# mpu9250.net
KiCad netlist of a schematic drawn in Altium Designer
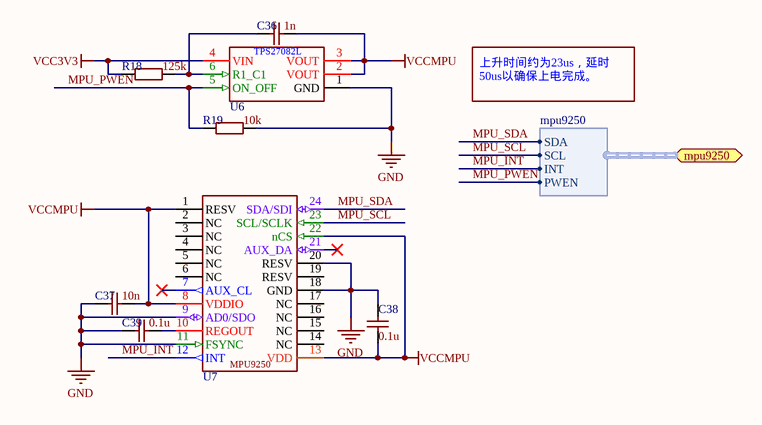
[diagram p0: mpu9250.SchDoc]

(export (version "E")
  (design (tool "Eeschema 10.0.6"))
  (components
    (comp (ref "C36")
      (value "1n")
      (footprint "C0402_h")
      (description "Capacitor")
      (fields (field (name "PUBLISHER") "Altium Limited"))
      (libsource (lib "电子元件封装库") (part "贴片电容-无极性"))
    )
    (comp (ref "C37")
      (value "10n")
      (footprint "C0402_h")
      (description "Capacitor")
      (fields (field (name "PUBLISHER") "Altium Limited"))
      (libsource (lib "电子元件封装库") (part "贴片电容-无极性"))
    )
    (comp (ref "C38")
      (value "0.1u")
      (footprint "C0402_h")
      (description "Capacitor")
      (fields (field (name "PUBLISHER") "Altium Limited"))
      (libsource (lib "电子元件封装库") (part "贴片电容-无极性"))
    )
    (comp (ref "C39")
      (value "0.1u")
      (footprint "C0402_h")
      (description "Capacitor")
      (fields (field (name "PUBLISHER") "Altium Limited"))
      (libsource (lib "电子元件封装库") (part "贴片电容-无极性"))
    )
    (comp (ref "R18")
      (value "125k")
      (footprint "R0402")
      (description "Register")
      (libsource (lib "电子元件封装库") (part "贴片电阻"))
    )
    (comp (ref "R19")
      (value "10k")
      (footprint "R0402")
      (description "Register")
      (libsource (lib "电子元件封装库") (part "贴片电阻"))
    )
    (comp (ref "U6")
      (value "TPS27082L")
      (footprint "SOT23-6")
      (description "load switch")
      (fields (field (name "PARTNUMBER") "TPS27082LDDC") (field (name "MANUFACTURER") "Texas Instruments"))
      (libsource (lib "电子元件封装库") (part "TPS27082LDDCR"))
    )
    (comp (ref "U7")
      (value "MPU9250")
      (footprint "QFN24 3.0X3.0")
      (description "9-axis MotionTracking Sensor")
      (libsource (lib "电子元件封装库") (part "MPU9250"))
    )
  )
  (nets
    (net (code "2") (name "/MPU_INT") (class "Default")
      (node (ref "U7") (pin "12") (pinfunction "INT_12") (pintype "output"))
    )
    (net (code "3") (name "/MPU_PWEN") (class "Default")
      (node (ref "R19") (pin "1") (pinfunction "1_1") (pintype "passive"))
      (node (ref "U6") (pin "5") (pinfunction "ON_OFF_5") (pintype "input"))
    )
    (net (code "4") (name "/MPU_SCL") (class "Default")
      (node (ref "U7") (pin "23") (pinfunction "SCL/SCLK_23") (pintype "input"))
    )
    (net (code "5") (name "/MPU_SDA") (class "Default")
      (node (ref "U7") (pin "24") (pinfunction "SDA/SDI_24") (pintype "bidirectional"))
    )
    (net (code "7") (name "GND") (class "Default")
      (node (ref "C37") (pin "1") (pinfunction "1_1") (pintype "passive"))
      (node (ref "C38") (pin "2") (pinfunction "2_2") (pintype "passive"))
      (node (ref "C39") (pin "1") (pinfunction "1_1") (pintype "passive"))
      (node (ref "R19") (pin "2") (pinfunction "2_2") (pintype "passive"))
      (node (ref "U6") (pin "1") (pinfunction "GND_1") (pintype "power_in"))
      (node (ref "U7") (pin "11") (pinfunction "FSYNC_11") (pintype "input"))
      (node (ref "U7") (pin "18") (pinfunction "GND_18") (pintype "power_in"))
      (node (ref "U7") (pin "20") (pinfunction "RESV_20") (pintype "passive"))
      (node (ref "U7") (pin "9") (pinfunction "AD0/SDO_9") (pintype "bidirectional"))
    )
    (net (code "8") (name "Net-(U6-R1_C1)") (class "Default")
      (node (ref "C36") (pin "1") (pinfunction "1_1") (pintype "passive"))
      (node (ref "R18") (pin "2") (pinfunction "2_2") (pintype "passive"))
      (node (ref "U6") (pin "6") (pinfunction "R1_C1_6") (pintype "input"))
    )
    (net (code "9") (name "Net-(U7-REGOUT)") (class "Default")
      (node (ref "C39") (pin "2") (pinfunction "2_2") (pintype "passive"))
      (node (ref "U7") (pin "10") (pinfunction "REGOUT_10") (pintype "power_in"))
    )
    (net (code "10") (name "VCC3V3") (class "Default")
      (node (ref "R18") (pin "1") (pinfunction "1_1") (pintype "passive"))
      (node (ref "U6") (pin "4") (pinfunction "VIN_4") (pintype "power_in"))
    )
    (net (code "11") (name "VCCMPU") (class "Default")
      (node (ref "C36") (pin "2") (pinfunction "2_2") (pintype "passive"))
      (node (ref "C37") (pin "2") (pinfunction "2_2") (pintype "passive"))
      (node (ref "C38") (pin "1") (pinfunction "1_1") (pintype "passive"))
      (node (ref "U6") (pin "2") (pinfunction "VOUT_2") (pintype "power_in"))
      (node (ref "U6") (pin "3") (pinfunction "VOUT_3") (pintype "power_in"))
      (node (ref "U7") (pin "1") (pinfunction "RESV_1") (pintype "passive"))
      (node (ref "U7") (pin "13") (pinfunction "VDD_13") (pintype "power_in"))
      (node (ref "U7") (pin "22") (pinfunction "nCS_22") (pintype "input"))
      (node (ref "U7") (pin "8") (pinfunction "VDDIO_8") (pintype "power_in"))
    )
    (net (code "12") (name "unconnected-(U7-AUX_CL-Pad7)") (class "Default")
      (node (ref "U7") (pin "7") (pinfunction "AUX_CL_7") (pintype "output+no_connect"))
    )
    (net (code "13") (name "unconnected-(U7-AUX_DA-Pad21)") (class "Default")
      (node (ref "U7") (pin "21") (pinfunction "AUX_DA_21") (pintype "bidirectional+no_connect"))
    )
    (net (code "14") (name "unconnected-(U7-NC-Pad2)") (class "Default")
      (node (ref "U7") (pin "2") (pinfunction "NC_2") (pintype "passive"))
    )
    (net (code "15") (name "unconnected-(U7-NC-Pad3)") (class "Default")
      (node (ref "U7") (pin "3") (pinfunction "NC_3") (pintype "passive"))
    )
    (net (code "16") (name "unconnected-(U7-NC-Pad4)") (class "Default")
      (node (ref "U7") (pin "4") (pinfunction "NC_4") (pintype "passive"))
    )
    (net (code "17") (name "unconnected-(U7-NC-Pad5)") (class "Default")
      (node (ref "U7") (pin "5") (pinfunction "NC_5") (pintype "passive"))
    )
    (net (code "18") (name "unconnected-(U7-NC-Pad6)") (class "Default")
      (node (ref "U7") (pin "6") (pinfunction "NC_6") (pintype "passive"))
    )
    (net (code "19") (name "unconnected-(U7-NC-Pad14)") (class "Default")
      (node (ref "U7") (pin "14") (pinfunction "NC_14") (pintype "passive"))
    )
    (net (code "20") (name "unconnected-(U7-NC-Pad15)") (class "Default")
      (node (ref "U7") (pin "15") (pinfunction "NC_15") (pintype "passive"))
    )
    (net (code "21") (name "unconnected-(U7-NC-Pad16)") (class "Default")
      (node (ref "U7") (pin "16") (pinfunction "NC_16") (pintype "passive"))
    )
    (net (code "22") (name "unconnected-(U7-NC-Pad17)") (class "Default")
      (node (ref "U7") (pin "17") (pinfunction "NC_17") (pintype "passive"))
    )
    (net (code "23") (name "unconnected-(U7-RESV-Pad19)") (class "Default")
      (node (ref "U7") (pin "19") (pinfunction "RESV_19") (pintype "passive"))
    )
  )
)
